# SCH_Personal-Card-V2_2024-07-09.net
KiCad netlist of a schematic drawn in EasyEDA
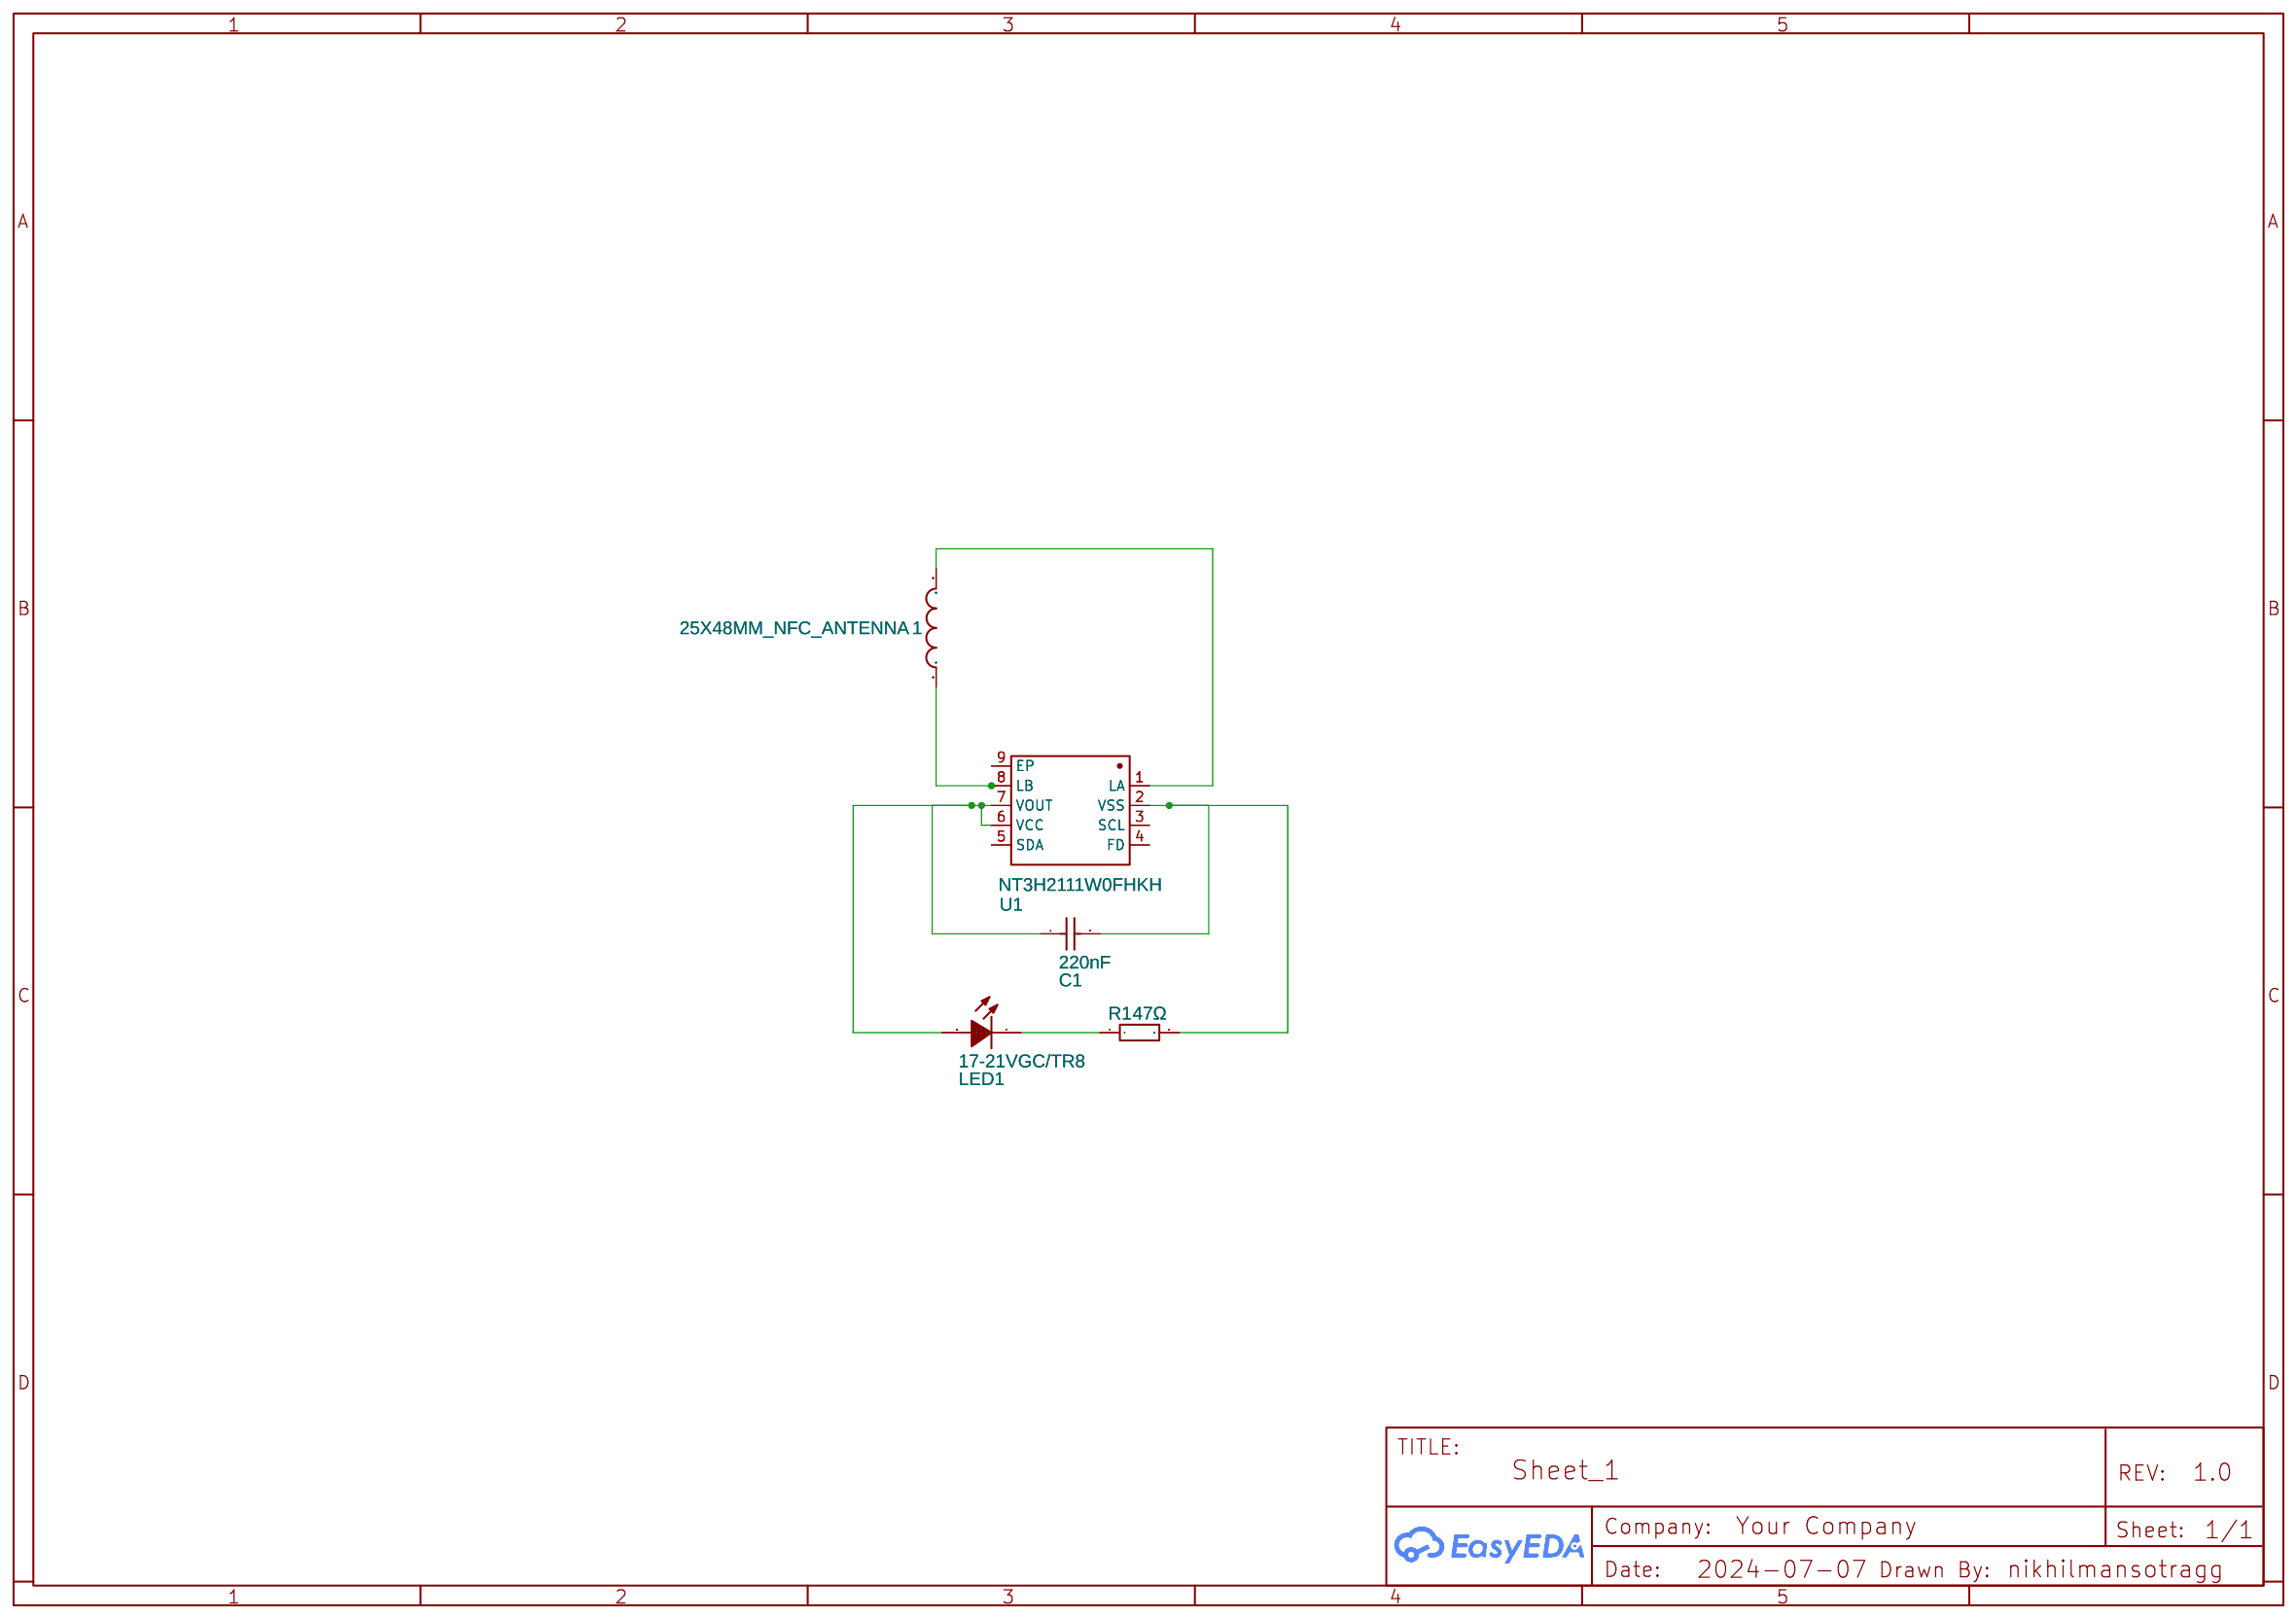
[diagram p0: schematic sheet]

(export (version "E")
  (design (tool "Eeschema 10.0.6"))
  (components
    (comp (ref "1") (value "25X48MM_NFC_ANTENNA") (libsource (lib "") (part "25X48MM_NFC_ANTENNA")))
    (comp (ref "C1")
      (value "220nF")
      (fields
        (field (name "Manufacturer Part") "CL10B224KA8NNNC")
        (field (name "Manufacturer") "SAMSUNG(三星)")
      )
      (libsource (lib "") (part "CL10B224KA8NNNC"))
    )
    (comp (ref "LED1")
      (value "17-21VGC/TR8")
      (fields (field (name "Manufacturer") "EVERLIGHT(亿光)"))
      (libsource (lib "") (part "17-21VGC/TR8"))
    )
    (comp (ref "R1")
      (value "47Ω")
      (fields
        (field (name "Manufacturer Part") "0603WAF470JT5E")
        (field (name "Manufacturer") "UNI-ROYAL(厚声)")
      )
      (libsource (lib "") (part "0603WAF470JT5E"))
    )
    (comp (ref "U1")
      (value "NT3H2111W0FHKH")
      (fields (field (name "Manufacturer") "NXP(恩智浦)"))
      (libsource (lib "") (part "NT3H2111W0FHKH"))
    )
  )
  (nets
    (net (code "1") (name "Net-(LED1-+)") (class "Default")
      (node (ref "C1") (pin "1") (pinfunction "1_1") (pintype "input"))
      (node (ref "LED1") (pin "2") (pinfunction "+_2") (pintype "unspecified"))
      (node (ref "U1") (pin "6") (pinfunction "VCC_6") (pintype "unspecified"))
      (node (ref "U1") (pin "7") (pinfunction "VOUT_7") (pintype "unspecified"))
    )
    (net (code "2") (name "Net-(LED1--)") (class "Default")
      (node (ref "LED1") (pin "1") (pinfunction "-_1") (pintype "unspecified"))
      (node (ref "R1") (pin "1") (pinfunction "1_1") (pintype "input"))
    )
    (net (code "3") (name "Net-(U1-LA)") (class "Default")
      (node (ref "1") (pin "P$2") (pinfunction "P$2_P$2") (pintype "bidirectional"))
      (node (ref "U1") (pin "1") (pinfunction "LA_1") (pintype "unspecified"))
    )
    (net (code "4") (name "Net-(U1-LB)") (class "Default")
      (node (ref "1") (pin "P$1") (pinfunction "P$1_P$1") (pintype "bidirectional"))
      (node (ref "U1") (pin "8") (pinfunction "LB_8") (pintype "unspecified"))
    )
    (net (code "5") (name "Net-(U1-VSS)") (class "Default")
      (node (ref "C1") (pin "2") (pinfunction "2_2") (pintype "input"))
      (node (ref "R1") (pin "2") (pinfunction "2_2") (pintype "input"))
      (node (ref "U1") (pin "2") (pinfunction "VSS_2") (pintype "unspecified"))
    )
    (net (code "6") (name "unconnected-(U1-EP-Pad9)") (class "Default")
      (node (ref "U1") (pin "9") (pinfunction "EP_9") (pintype "unspecified"))
    )
    (net (code "7") (name "unconnected-(U1-FD-Pad4)") (class "Default")
      (node (ref "U1") (pin "4") (pinfunction "FD_4") (pintype "unspecified"))
    )
    (net (code "8") (name "unconnected-(U1-SCL-Pad3)") (class "Default")
      (node (ref "U1") (pin "3") (pinfunction "SCL_3") (pintype "unspecified"))
    )
    (net (code "9") (name "unconnected-(U1-SDA-Pad5)") (class "Default")
      (node (ref "U1") (pin "5") (pinfunction "SDA_5") (pintype "unspecified"))
    )
  )
)
